# AQM2b.net
KiCad netlist of a schematic drawn in EasyEDA Pro
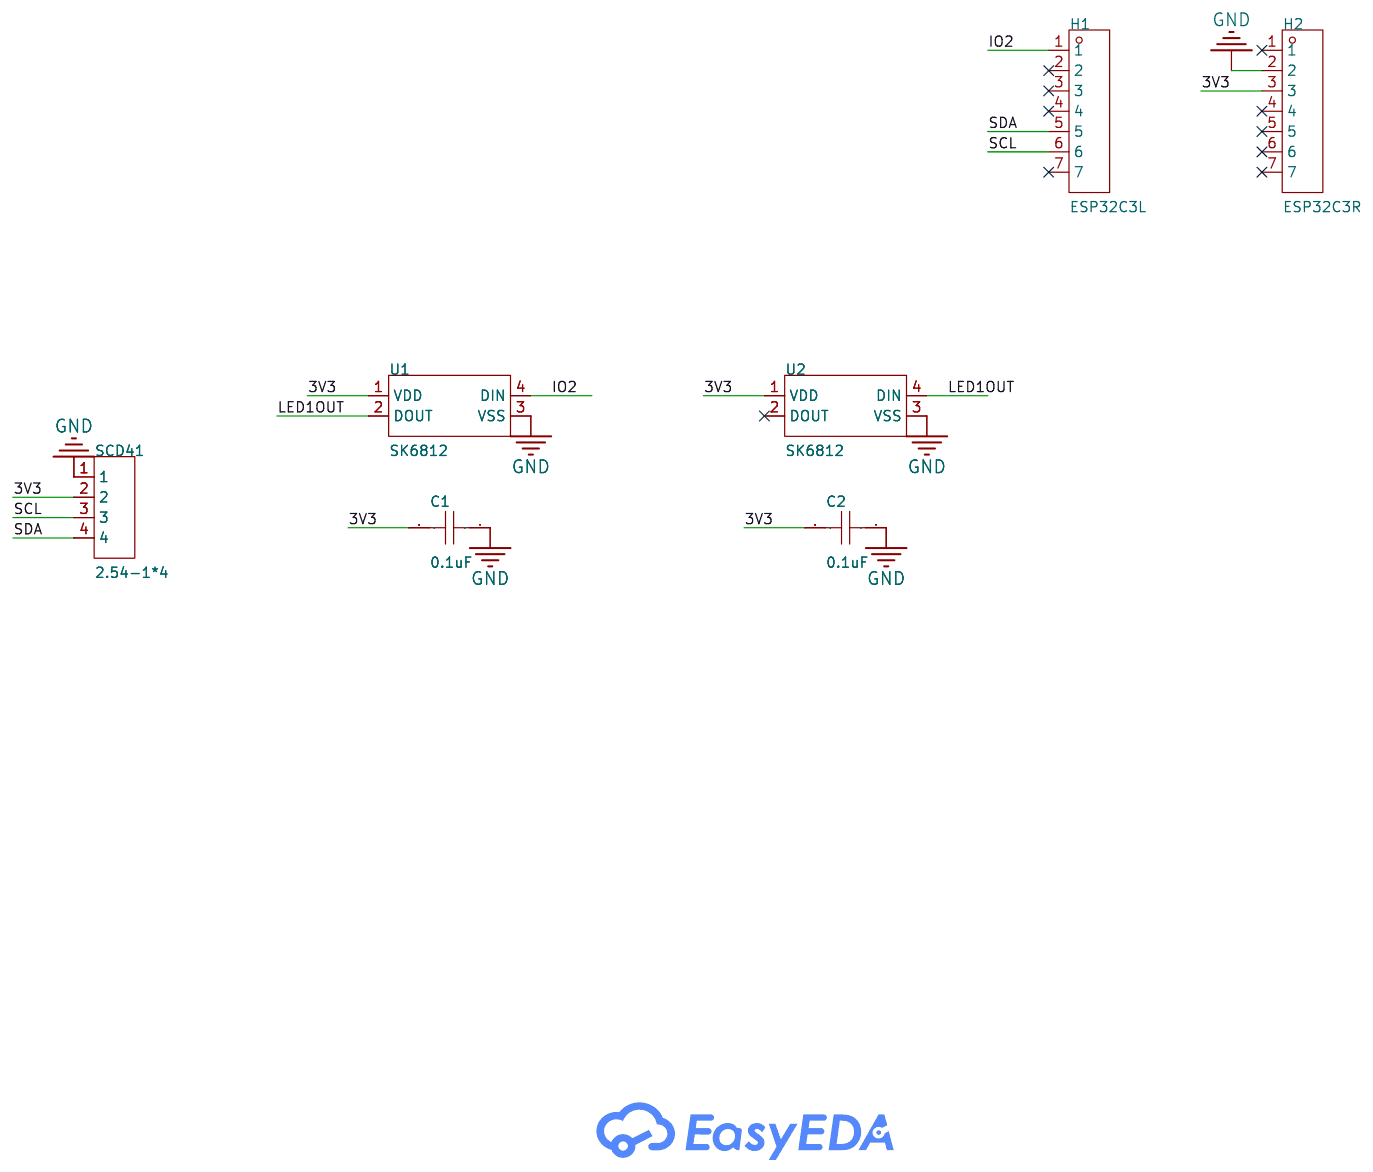
[diagram p0: schematic sheet]

(export (version "E")
  (design (tool "Eeschema 10.0.6"))
  (components
    (comp (ref "C1")
      (value "0.1uF")
      (footprint "easyedapro:C0603")
      (libsource (lib "easyedapro") (part "CAP"))
    )
    (comp (ref "C2")
      (value "0.1uF")
      (footprint "easyedapro:C0603")
      (libsource (lib "easyedapro") (part "CAP"))
    )
    (comp (ref "H1")
      (value "ESP32C3L")
      (footprint "easyedapro:HDR-TH_7P-P2.54-V-M")
      (fields (field (name "Manufacturer") "hanxia(韩下)"))
      (libsource (lib "easyedapro") (part "HX PZ2.54-1X7P ZZ"))
    )
    (comp (ref "H2")
      (value "ESP32C3R")
      (footprint "easyedapro:HDR-TH_7P-P2.54-V-M")
      (fields (field (name "Manufacturer") "hanxia(韩下)"))
      (libsource (lib "easyedapro") (part "HX PZ2.54-1X7P ZZ"))
    )
    (comp (ref "SCD41")
      (value "2.54-1*4")
      (footprint "easyedapro:HDR-TH_4P-P2.54-V-M-1")
      (fields (field (name "Manufacturer") "ZHOURI(洲日)"))
      (libsource (lib "easyedapro") (part "2.54-1*4"))
    )
    (comp (ref "U1")
      (value "SK6812")
      (footprint "easyedapro:LED-SMD_4P-L5.0-W5.0-LS5.4-TL-1")
      (fields (field (name "Manufacturer") "欧思科光电"))
      (libsource (lib "easyedapro") (part "SK6812_C5378720"))
    )
    (comp (ref "U2")
      (value "SK6812")
      (footprint "easyedapro:LED-SMD_4P-L5.0-W5.0-LS5.4-TL-1")
      (fields (field (name "Manufacturer") "欧思科光电"))
      (libsource (lib "easyedapro") (part "SK6812_C5378720"))
    )
  )
  (nets
    (net (code "1") (name "/3V3") (class "Default")
      (node (ref "C1") (pin "2") (pinfunction "2_2") (pintype "input"))
      (node (ref "C2") (pin "2") (pinfunction "2_2") (pintype "input"))
      (node (ref "H2") (pin "3") (pinfunction "3_3") (pintype "unspecified"))
      (node (ref "SCD41") (pin "2") (pinfunction "2_2") (pintype "unspecified"))
      (node (ref "U1") (pin "1") (pinfunction "VDD_1") (pintype "unspecified"))
      (node (ref "U2") (pin "1") (pinfunction "VDD_1") (pintype "unspecified"))
    )
    (net (code "2") (name "/IO2") (class "Default")
      (node (ref "H1") (pin "1") (pinfunction "1_1") (pintype "unspecified"))
      (node (ref "U1") (pin "4") (pinfunction "DIN_4") (pintype "unspecified"))
    )
    (net (code "3") (name "/LED1OUT") (class "Default")
      (node (ref "U1") (pin "2") (pinfunction "DOUT_2") (pintype "unspecified"))
      (node (ref "U2") (pin "4") (pinfunction "DIN_4") (pintype "unspecified"))
    )
    (net (code "4") (name "/SCL") (class "Default")
      (node (ref "H1") (pin "6") (pinfunction "6_6") (pintype "unspecified"))
      (node (ref "SCD41") (pin "3") (pinfunction "3_3") (pintype "unspecified"))
    )
    (net (code "5") (name "/SDA") (class "Default")
      (node (ref "H1") (pin "5") (pinfunction "5_5") (pintype "unspecified"))
      (node (ref "SCD41") (pin "4") (pinfunction "4_4") (pintype "unspecified"))
    )
    (net (code "6") (name "GND") (class "Default")
      (node (ref "C1") (pin "1") (pinfunction "1_1") (pintype "input"))
      (node (ref "C2") (pin "1") (pinfunction "1_1") (pintype "input"))
      (node (ref "H2") (pin "2") (pinfunction "2_2") (pintype "unspecified"))
      (node (ref "SCD41") (pin "1") (pinfunction "1_1") (pintype "unspecified"))
      (node (ref "U1") (pin "3") (pinfunction "VSS_3") (pintype "unspecified"))
      (node (ref "U2") (pin "3") (pinfunction "VSS_3") (pintype "unspecified"))
    )
    (net (code "7") (name "unconnected-(H1-Pad2)") (class "Default")
      (node (ref "H1") (pin "2") (pinfunction "2_2") (pintype "unspecified+no_connect"))
    )
    (net (code "8") (name "unconnected-(H1-Pad3)") (class "Default")
      (node (ref "H1") (pin "3") (pinfunction "3_3") (pintype "unspecified+no_connect"))
    )
    (net (code "9") (name "unconnected-(H1-Pad4)") (class "Default")
      (node (ref "H1") (pin "4") (pinfunction "4_4") (pintype "unspecified+no_connect"))
    )
    (net (code "10") (name "unconnected-(H1-Pad7)") (class "Default")
      (node (ref "H1") (pin "7") (pinfunction "7_7") (pintype "unspecified+no_connect"))
    )
    (net (code "11") (name "unconnected-(H2-Pad1)") (class "Default")
      (node (ref "H2") (pin "1") (pinfunction "1_1") (pintype "unspecified+no_connect"))
    )
    (net (code "12") (name "unconnected-(H2-Pad4)") (class "Default")
      (node (ref "H2") (pin "4") (pinfunction "4_4") (pintype "unspecified+no_connect"))
    )
    (net (code "13") (name "unconnected-(H2-Pad5)") (class "Default")
      (node (ref "H2") (pin "5") (pinfunction "5_5") (pintype "unspecified+no_connect"))
    )
    (net (code "14") (name "unconnected-(H2-Pad6)") (class "Default")
      (node (ref "H2") (pin "6") (pinfunction "6_6") (pintype "unspecified+no_connect"))
    )
    (net (code "15") (name "unconnected-(H2-Pad7)") (class "Default")
      (node (ref "H2") (pin "7") (pinfunction "7_7") (pintype "unspecified+no_connect"))
    )
    (net (code "16") (name "unconnected-(U2-DOUT-Pad2)") (class "Default")
      (node (ref "U2") (pin "2") (pinfunction "DOUT_2") (pintype "unspecified+no_connect"))
    )
  )
)
